# GEX_Radio.net
KiCad netlist of a schematic drawn in Altium Designer
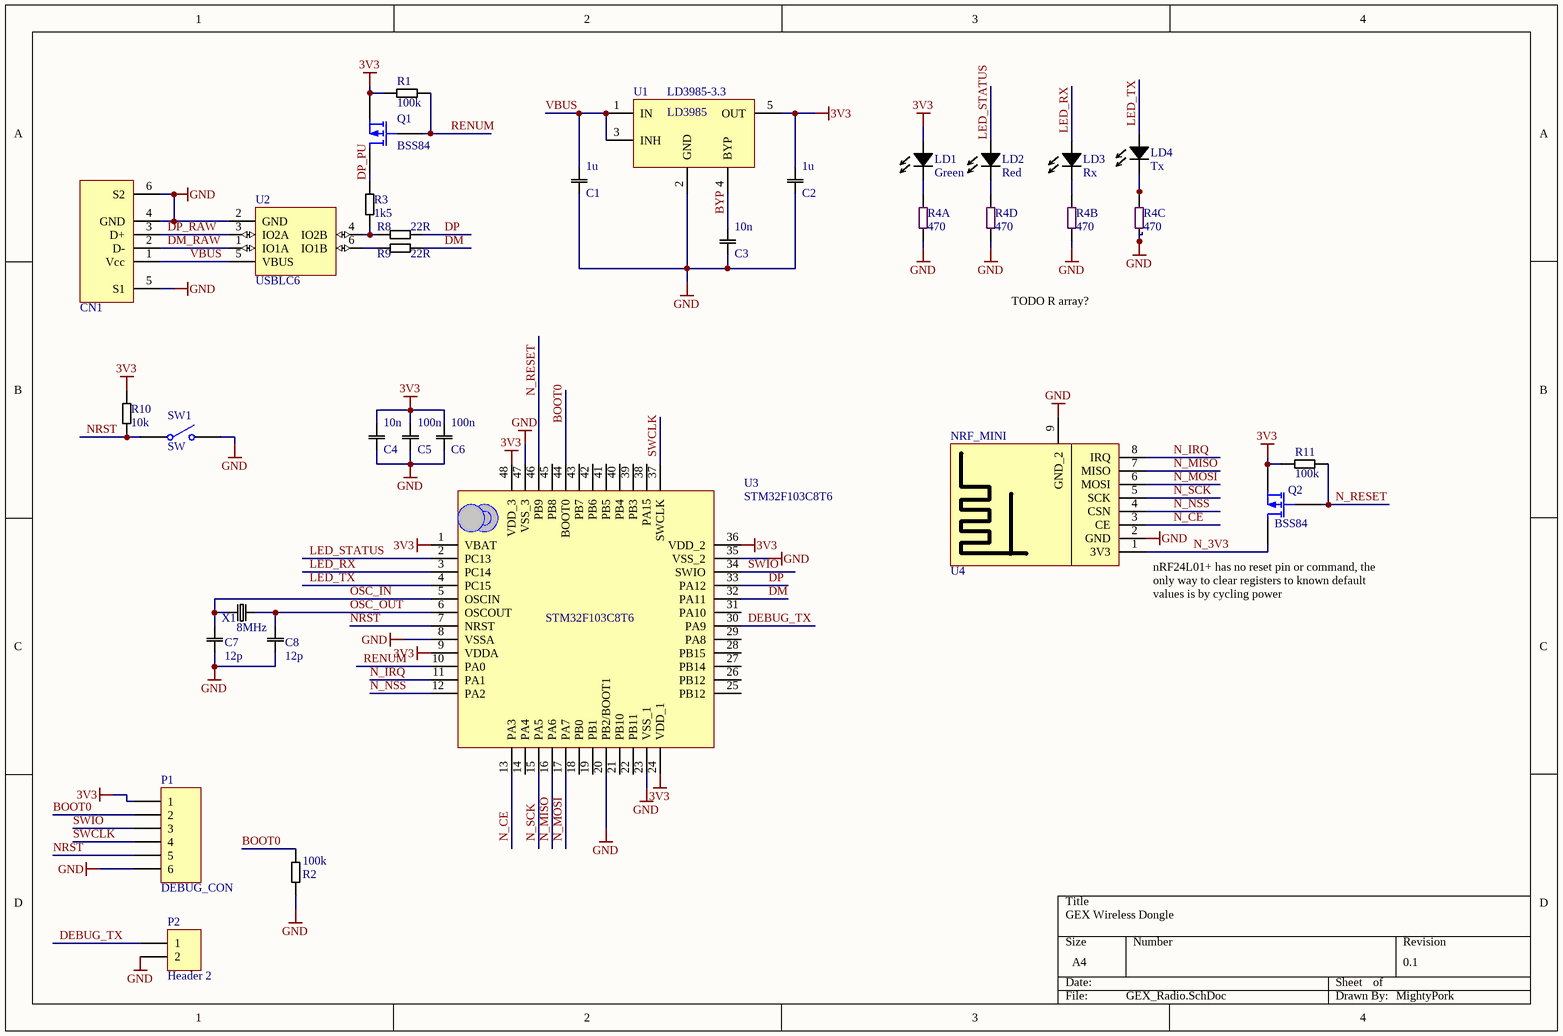
[diagram p0: GEX_Radio.SchDoc]

(export (version "E")
  (design (tool "Eeschema 10.0.6"))
  (components
    (comp (ref "C1")
      (value "1u")
      (footprint "ABU_standard:C0805")
      (libsource (lib "ABU_standard") (part "C"))
    )
    (comp (ref "C2")
      (value "1u")
      (footprint "ABU_standard:C0805")
      (libsource (lib "ABU_standard") (part "C"))
    )
    (comp (ref "C3")
      (value "10n")
      (footprint "ABU_standard:C0805")
      (libsource (lib "ABU_standard") (part "C"))
    )
    (comp (ref "C4")
      (value "10n")
      (footprint "ABU_standard:C0805")
      (libsource (lib "ABU_standard") (part "C"))
    )
    (comp (ref "C5")
      (value "100n")
      (footprint "ABU_standard:C0805")
      (libsource (lib "ABU_standard") (part "C"))
    )
    (comp (ref "C6")
      (value "100n")
      (footprint "ABU_standard:C0805")
      (libsource (lib "ABU_standard") (part "C"))
    )
    (comp (ref "C7")
      (value "12p")
      (footprint "ABU_standard:C0805")
      (libsource (lib "ABU_standard") (part "C"))
    )
    (comp (ref "C8")
      (value "12p")
      (footprint "ABU_standard:C0805")
      (libsource (lib "ABU_standard") (part "C"))
    )
    (comp (ref "CN1") (value "USB_A") (footprint "CUSTOM:USB_A") (libsource (lib "CUSTOM") (part "USB_A")))
    (comp (ref "LD1") (value "Green") (footprint "LED_SMD") (libsource (lib "ABU_standard") (part "LED")))
    (comp (ref "LD2") (value "Red") (footprint "LED_SMD") (libsource (lib "ABU_standard") (part "LED")))
    (comp (ref "LD3") (value "Rx") (footprint "LED_SMD") (libsource (lib "ABU_standard") (part "LED")))
    (comp (ref "LD4") (value "Tx") (footprint "LED_SMD") (libsource (lib "ABU_standard") (part "LED")))
    (comp (ref "P1")
      (value "DEBUG_CON")
      (footprint "Header_6_2mm")
      (description "Header, 6-Pin")
      (fields (field (name "PUBLISHER") "Altium Limited"))
      (libsource (lib "Miscellaneous Connectors") (part "Header 6"))
    )
    (comp (ref "P2")
      (value "Header 2")
      (footprint "Header_2_2mm")
      (description "Header, 2-Pin")
      (fields (field (name "Comment") "Header_2"))
      (libsource (lib "CONN") (part "Header_2"))
    )
    (comp (ref "Q1")
      (value "BSS84")
      (footprint "SOT23")
      (description "P-Channel Enhancement Mode Vertical DMOS FET")
      (libsource (lib "ABU_standard") (part "BSS84"))
    )
    (comp (ref "Q2")
      (value "BSS84")
      (footprint "SOT23")
      (description "P-Channel Enhancement Mode Vertical DMOS FET")
      (libsource (lib "ABU_standard") (part "BSS84"))
    )
    (comp (ref "R1") (value "100k") (footprint "R0805") (libsource (lib "ABU_standard") (part "R")))
    (comp (ref "R2") (value "100k") (footprint "R0805") (libsource (lib "") (part "R_2")))
    (comp (ref "R3") (value "1k5") (footprint "R0805") (libsource (lib "") (part "R_1")))
    (comp (ref "R4") (value "470") (footprint "R1206_Array_longpad") (libsource (lib "") (part "R_ARRAY_1")))
    (comp (ref "R8") (value "22R") (footprint "R0805") (libsource (lib "ABU_standard") (part "R")))
    (comp (ref "R9") (value "22R") (footprint "R0805") (libsource (lib "ABU_standard") (part "R")))
    (comp (ref "R10") (value "10k") (footprint "R0805") (libsource (lib "") (part "R_2")))
    (comp (ref "R11") (value "100k") (footprint "R0805") (libsource (lib "ABU_standard") (part "R")))
    (comp (ref "SW1")
      (value "SW")
      (footprint "SW_TINY_4PAD")
      (libsource (lib "CUSTOM") (part "SW_SPST_4PAD"))
    )
    (comp (ref "U1") (value "LD3985-3.3") (footprint "SOT23-5") (libsource (lib "CUSTOM") (part "LD3985")))
    (comp (ref "U2") (value "USBLC6") (footprint "SOT23-6") (libsource (lib "CUSTOM") (part "USBLC6_ESD")))
    (comp (ref "U3")
      (value "STM32F103C8T6")
      (footprint "LQFP48_SHORT")
      (libsource (lib "CUSTOM") (part "STM32F103C8T6"))
    )
    (comp (ref "U4")
      (value "NRF_MINI")
      (footprint "NRF_MINI_NOANTLINES")
      (libsource (lib "CUSTOM") (part "NRF_MINI"))
    )
    (comp (ref "X1")
      (value "8MHz")
      (footprint "XTAL-SMD-50-32")
      (libsource (lib "ABU_standard") (part "XTALL"))
    )
  )
  (nets
    (net (code "1") (name "/BOOT0") (class "Default")
      (node (ref "P1") (pin "2") (pinfunction "2_2") (pintype "passive"))
      (node (ref "R2") (pin "1") (pinfunction "1_1") (pintype "passive"))
      (node (ref "U3") (pin "44") (pinfunction "BOOT0_44") (pintype "passive"))
    )
    (net (code "2") (name "/BYP") (class "Default")
      (node (ref "C3") (pin "2") (pinfunction "2_2") (pintype "passive"))
      (node (ref "U1") (pin "4") (pinfunction "BYP_4") (pintype "passive"))
    )
    (net (code "3") (name "/DEBUG_TX") (class "Default")
      (node (ref "P2") (pin "1") (pinfunction "1_1") (pintype "passive"))
      (node (ref "U3") (pin "30") (pinfunction "PA9_30") (pintype "passive"))
    )
    (net (code "4") (name "/DM") (class "Default")
      (node (ref "R9") (pin "1") (pinfunction "1_1") (pintype "passive"))
      (node (ref "U3") (pin "32") (pinfunction "PA11_32") (pintype "passive"))
    )
    (net (code "5") (name "/DM_RAW") (class "Default")
      (node (ref "CN1") (pin "2") (pinfunction "D-_2") (pintype "power_in"))
      (node (ref "U2") (pin "1") (pinfunction "IO1A_1") (pintype "bidirectional"))
    )
    (net (code "6") (name "/DP") (class "Default")
      (node (ref "R8") (pin "1") (pinfunction "1_1") (pintype "passive"))
      (node (ref "U3") (pin "33") (pinfunction "PA12_33") (pintype "passive"))
    )
    (net (code "7") (name "/DP_PU") (class "Default")
      (node (ref "Q1") (pin "3") (pinfunction "D_3") (pintype "passive"))
      (node (ref "R3") (pin "2") (pinfunction "2_2") (pintype "passive"))
    )
    (net (code "8") (name "/DP_RAW") (class "Default")
      (node (ref "CN1") (pin "3") (pinfunction "D+_3") (pintype "power_in"))
      (node (ref "U2") (pin "3") (pinfunction "IO2A_3") (pintype "bidirectional"))
    )
    (net (code "9") (name "/LED_RX") (class "Default")
      (node (ref "LD3") (pin "A") (pinfunction "A_A") (pintype "passive"))
      (node (ref "U3") (pin "3") (pinfunction "PC14_3") (pintype "passive"))
    )
    (net (code "10") (name "/LED_STATUS") (class "Default")
      (node (ref "LD2") (pin "A") (pinfunction "A_A") (pintype "passive"))
      (node (ref "U3") (pin "2") (pinfunction "PC13_2") (pintype "passive"))
    )
    (net (code "11") (name "/LED_TX") (class "Default")
      (node (ref "LD4") (pin "A") (pinfunction "A_A") (pintype "passive"))
      (node (ref "U3") (pin "4") (pinfunction "PC15_4") (pintype "passive"))
    )
    (net (code "12") (name "/NRST") (class "Default")
      (node (ref "P1") (pin "5") (pinfunction "5_5") (pintype "passive"))
      (node (ref "R10") (pin "2") (pinfunction "2_2") (pintype "passive"))
      (node (ref "SW1") (pin "1") (pinfunction "COMMON_1") (pintype "passive"))
      (node (ref "U3") (pin "7") (pinfunction "NRST_7") (pintype "passive"))
    )
    (net (code "13") (name "/N_3V3") (class "Default")
      (node (ref "Q2") (pin "3") (pinfunction "D_3") (pintype "passive"))
      (node (ref "U4") (pin "1") (pinfunction "3V3_1") (pintype "power_in"))
    )
    (net (code "14") (name "/N_CE") (class "Default")
      (node (ref "U3") (pin "13") (pinfunction "PA3_13") (pintype "passive"))
      (node (ref "U4") (pin "3") (pinfunction "CE_3") (pintype "power_in"))
    )
    (net (code "15") (name "/N_IRQ") (class "Default")
      (node (ref "U3") (pin "11") (pinfunction "PA1_11") (pintype "passive"))
      (node (ref "U4") (pin "8") (pinfunction "IRQ_8") (pintype "power_in"))
    )
    (net (code "16") (name "/N_MISO") (class "Default")
      (node (ref "U3") (pin "16") (pinfunction "PA6_16") (pintype "passive"))
      (node (ref "U4") (pin "7") (pinfunction "MISO_7") (pintype "power_in"))
    )
    (net (code "17") (name "/N_MOSI") (class "Default")
      (node (ref "U3") (pin "17") (pinfunction "PA7_17") (pintype "passive"))
      (node (ref "U4") (pin "6") (pinfunction "MOSI_6") (pintype "power_in"))
    )
    (net (code "18") (name "/N_NSS") (class "Default")
      (node (ref "U3") (pin "12") (pinfunction "PA2_12") (pintype "passive"))
      (node (ref "U4") (pin "4") (pinfunction "CSN_4") (pintype "power_in"))
    )
    (net (code "19") (name "/N_RESET") (class "Default")
      (node (ref "Q2") (pin "1") (pinfunction "G_1") (pintype "passive"))
      (node (ref "R11") (pin "1") (pinfunction "1_1") (pintype "passive"))
      (node (ref "U3") (pin "46") (pinfunction "PB9_46") (pintype "passive"))
    )
    (net (code "20") (name "/N_SCK") (class "Default")
      (node (ref "U3") (pin "15") (pinfunction "PA5_15") (pintype "passive"))
      (node (ref "U4") (pin "5") (pinfunction "SCK_5") (pintype "power_in"))
    )
    (net (code "21") (name "/OSC_IN") (class "Default")
      (node (ref "C7") (pin "2") (pinfunction "2_2") (pintype "passive"))
      (node (ref "U3") (pin "5") (pinfunction "OSCIN_5") (pintype "passive"))
      (node (ref "X1") (pin "1") (pinfunction "1_1") (pintype "passive"))
    )
    (net (code "22") (name "/OSC_OUT") (class "Default")
      (node (ref "C8") (pin "2") (pinfunction "2_2") (pintype "passive"))
      (node (ref "U3") (pin "6") (pinfunction "OSCOUT_6") (pintype "passive"))
      (node (ref "X1") (pin "2") (pinfunction "2_2") (pintype "passive"))
    )
    (net (code "23") (name "/RENUM") (class "Default")
      (node (ref "Q1") (pin "1") (pinfunction "G_1") (pintype "passive"))
      (node (ref "R1") (pin "1") (pinfunction "1_1") (pintype "passive"))
      (node (ref "U3") (pin "10") (pinfunction "PA0_10") (pintype "passive"))
    )
    (net (code "24") (name "/SWCLK") (class "Default")
      (node (ref "P1") (pin "4") (pinfunction "4_4") (pintype "passive"))
      (node (ref "U3") (pin "37") (pinfunction "SWCLK_37") (pintype "passive"))
    )
    (net (code "25") (name "/SWIO") (class "Default")
      (node (ref "P1") (pin "3") (pinfunction "3_3") (pintype "passive"))
      (node (ref "U3") (pin "34") (pinfunction "SWIO_34") (pintype "passive"))
    )
    (net (code "26") (name "/VBUS") (class "Default")
      (node (ref "C1") (pin "2") (pinfunction "2_2") (pintype "passive"))
      (node (ref "CN1") (pin "1") (pinfunction "Vcc_1") (pintype "power_in"))
      (node (ref "U1") (pin "1") (pinfunction "IN_1") (pintype "power_in"))
      (node (ref "U1") (pin "3") (pinfunction "INH_3") (pintype "passive"))
      (node (ref "U2") (pin "5") (pinfunction "VBUS_5") (pintype "power_in"))
    )
    (net (code "27") (name "3V3") (class "Default")
      (node (ref "C2") (pin "2") (pinfunction "2_2") (pintype "passive"))
      (node (ref "C4") (pin "2") (pinfunction "2_2") (pintype "passive"))
      (node (ref "C5") (pin "2") (pinfunction "2_2") (pintype "passive"))
      (node (ref "C6") (pin "2") (pinfunction "2_2") (pintype "passive"))
      (node (ref "LD1") (pin "A") (pinfunction "A_A") (pintype "passive"))
      (node (ref "P1") (pin "1") (pinfunction "1_1") (pintype "passive"))
      (node (ref "Q1") (pin "2") (pinfunction "S_2") (pintype "passive"))
      (node (ref "Q2") (pin "2") (pinfunction "S_2") (pintype "passive"))
      (node (ref "R1") (pin "2") (pinfunction "2_2") (pintype "passive"))
      (node (ref "R10") (pin "1") (pinfunction "1_1") (pintype "passive"))
      (node (ref "R11") (pin "2") (pinfunction "2_2") (pintype "passive"))
      (node (ref "U1") (pin "5") (pinfunction "OUT_5") (pintype "power_in"))
      (node (ref "U3") (pin "1") (pinfunction "VBAT_1") (pintype "passive"))
      (node (ref "U3") (pin "24") (pinfunction "VDD_1_24") (pintype "passive"))
      (node (ref "U3") (pin "36") (pinfunction "VDD_2_36") (pintype "passive"))
      (node (ref "U3") (pin "48") (pinfunction "VDD_3_48") (pintype "passive"))
      (node (ref "U3") (pin "9") (pinfunction "VDDA_9") (pintype "passive"))
    )
    (net (code "28") (name "GND") (class "Default")
      (node (ref "C1") (pin "1") (pinfunction "1_1") (pintype "passive"))
      (node (ref "C2") (pin "1") (pinfunction "1_1") (pintype "passive"))
      (node (ref "C3") (pin "1") (pinfunction "1_1") (pintype "passive"))
      (node (ref "C4") (pin "1") (pinfunction "1_1") (pintype "passive"))
      (node (ref "C5") (pin "1") (pinfunction "1_1") (pintype "passive"))
      (node (ref "C6") (pin "1") (pinfunction "1_1") (pintype "passive"))
      (node (ref "C7") (pin "1") (pinfunction "1_1") (pintype "passive"))
      (node (ref "C8") (pin "1") (pinfunction "1_1") (pintype "passive"))
      (node (ref "CN1") (pin "4") (pinfunction "GND_4") (pintype "power_in"))
      (node (ref "CN1") (pin "5") (pinfunction "S1_5") (pintype "power_in"))
      (node (ref "CN1") (pin "6") (pinfunction "S2_6") (pintype "power_in"))
      (node (ref "P1") (pin "6") (pinfunction "6_6") (pintype "passive"))
      (node (ref "P2") (pin "2") (pinfunction "2_2") (pintype "passive"))
      (node (ref "R2") (pin "2") (pinfunction "2_2") (pintype "passive"))
      (node (ref "R4") (pin "2") (pinfunction "2_2") (pintype "passive"))
      (node (ref "R4") (pin "4") (pinfunction "1_4") (pintype "passive"))
      (node (ref "R4") (pin "6") (pinfunction "1_6") (pintype "passive"))
      (node (ref "R4") (pin "8") (pinfunction "1_8") (pintype "passive"))
      (node (ref "SW1") (pin "2") (pinfunction "NO_2") (pintype "passive"))
      (node (ref "U1") (pin "2") (pinfunction "GND_2") (pintype "power_in"))
      (node (ref "U2") (pin "2") (pinfunction "GND_2") (pintype "power_in"))
      (node (ref "U3") (pin "20") (pinfunction "PB2/BOOT1_20") (pintype "passive"))
      (node (ref "U3") (pin "23") (pinfunction "VSS_1_23") (pintype "passive"))
      (node (ref "U3") (pin "35") (pinfunction "VSS_2_35") (pintype "passive"))
      (node (ref "U3") (pin "47") (pinfunction "VSS_3_47") (pintype "passive"))
      (node (ref "U3") (pin "8") (pinfunction "VSSA_8") (pintype "passive"))
      (node (ref "U4") (pin "2") (pinfunction "GND_2") (pintype "power_in"))
      (node (ref "U4") (pin "9") (pinfunction "GND_2_9") (pintype "power_in"))
    )
    (net (code "29") (name "Net-(LD1-PadC)") (class "Default")
      (node (ref "LD1") (pin "C") (pinfunction "C_C") (pintype "passive"))
      (node (ref "R4") (pin "1") (pinfunction "1_1") (pintype "passive"))
    )
    (net (code "30") (name "Net-(R4B-2)") (class "Default")
      (node (ref "LD3") (pin "C") (pinfunction "C_C") (pintype "passive"))
      (node (ref "R4") (pin "3") (pinfunction "2_3") (pintype "passive"))
    )
    (net (code "31") (name "Net-(R4C-2)") (class "Default")
      (node (ref "LD4") (pin "C") (pinfunction "C_C") (pintype "passive"))
      (node (ref "R4") (pin "5") (pinfunction "2_5") (pintype "passive"))
    )
    (net (code "32") (name "Net-(R4D-2)") (class "Default")
      (node (ref "LD2") (pin "C") (pinfunction "C_C") (pintype "passive"))
      (node (ref "R4") (pin "7") (pinfunction "2_7") (pintype "passive"))
    )
    (net (code "33") (name "Net-(U2-IO1B)") (class "Default")
      (node (ref "R9") (pin "2") (pinfunction "2_2") (pintype "passive"))
      (node (ref "U2") (pin "6") (pinfunction "IO1B_6") (pintype "bidirectional"))
    )
    (net (code "34") (name "Net-(U2-IO2B)") (class "Default")
      (node (ref "R3") (pin "1") (pinfunction "1_1") (pintype "passive"))
      (node (ref "R8") (pin "2") (pinfunction "2_2") (pintype "passive"))
      (node (ref "U2") (pin "4") (pinfunction "IO2B_4") (pintype "bidirectional"))
    )
    (net (code "35") (name "unconnected-(U3-PA4-Pad14)") (class "Default")
      (node (ref "U3") (pin "14") (pinfunction "PA4_14") (pintype "passive"))
    )
    (net (code "36") (name "unconnected-(U3-PA8-Pad29)") (class "Default")
      (node (ref "U3") (pin "29") (pinfunction "PA8_29") (pintype "passive"))
    )
    (net (code "37") (name "unconnected-(U3-PA10-Pad31)") (class "Default")
      (node (ref "U3") (pin "31") (pinfunction "PA10_31") (pintype "passive"))
    )
    (net (code "38") (name "unconnected-(U3-PA15-Pad38)") (class "Default")
      (node (ref "U3") (pin "38") (pinfunction "PA15_38") (pintype "passive"))
    )
    (net (code "39") (name "unconnected-(U3-PB0-Pad18)") (class "Default")
      (node (ref "U3") (pin "18") (pinfunction "PB0_18") (pintype "passive"))
    )
    (net (code "40") (name "unconnected-(U3-PB1-Pad19)") (class "Default")
      (node (ref "U3") (pin "19") (pinfunction "PB1_19") (pintype "passive"))
    )
    (net (code "41") (name "unconnected-(U3-PB3-Pad39)") (class "Default")
      (node (ref "U3") (pin "39") (pinfunction "PB3_39") (pintype "passive"))
    )
    (net (code "42") (name "unconnected-(U3-PB4-Pad40)") (class "Default")
      (node (ref "U3") (pin "40") (pinfunction "PB4_40") (pintype "passive"))
    )
    (net (code "43") (name "unconnected-(U3-PB5-Pad41)") (class "Default")
      (node (ref "U3") (pin "41") (pinfunction "PB5_41") (pintype "passive"))
    )
    (net (code "44") (name "unconnected-(U3-PB6-Pad42)") (class "Default")
      (node (ref "U3") (pin "42") (pinfunction "PB6_42") (pintype "passive"))
    )
    (net (code "45") (name "unconnected-(U3-PB7-Pad43)") (class "Default")
      (node (ref "U3") (pin "43") (pinfunction "PB7_43") (pintype "passive"))
    )
    (net (code "46") (name "unconnected-(U3-PB8-Pad45)") (class "Default")
      (node (ref "U3") (pin "45") (pinfunction "PB8_45") (pintype "passive"))
    )
    (net (code "47") (name "unconnected-(U3-PB10-Pad21)") (class "Default")
      (node (ref "U3") (pin "21") (pinfunction "PB10_21") (pintype "passive"))
    )
    (net (code "48") (name "unconnected-(U3-PB11-Pad22)") (class "Default")
      (node (ref "U3") (pin "22") (pinfunction "PB11_22") (pintype "passive"))
    )
    (net (code "49") (name "unconnected-(U3-PB12-Pad25)") (class "Default")
      (node (ref "U3") (pin "25") (pinfunction "PB12_25") (pintype "passive"))
    )
    (net (code "50") (name "unconnected-(U3-PB12-Pad26)") (class "Default")
      (node (ref "U3") (pin "26") (pinfunction "PB12_26") (pintype "passive"))
    )
    (net (code "51") (name "unconnected-(U3-PB14-Pad27)") (class "Default")
      (node (ref "U3") (pin "27") (pinfunction "PB14_27") (pintype "passive"))
    )
    (net (code "52") (name "unconnected-(U3-PB15-Pad28)") (class "Default")
      (node (ref "U3") (pin "28") (pinfunction "PB15_28") (pintype "passive"))
    )
  )
)
